# SKY13575-639LF_1to4.net
KiCad netlist of a schematic drawn in EasyEDA Pro
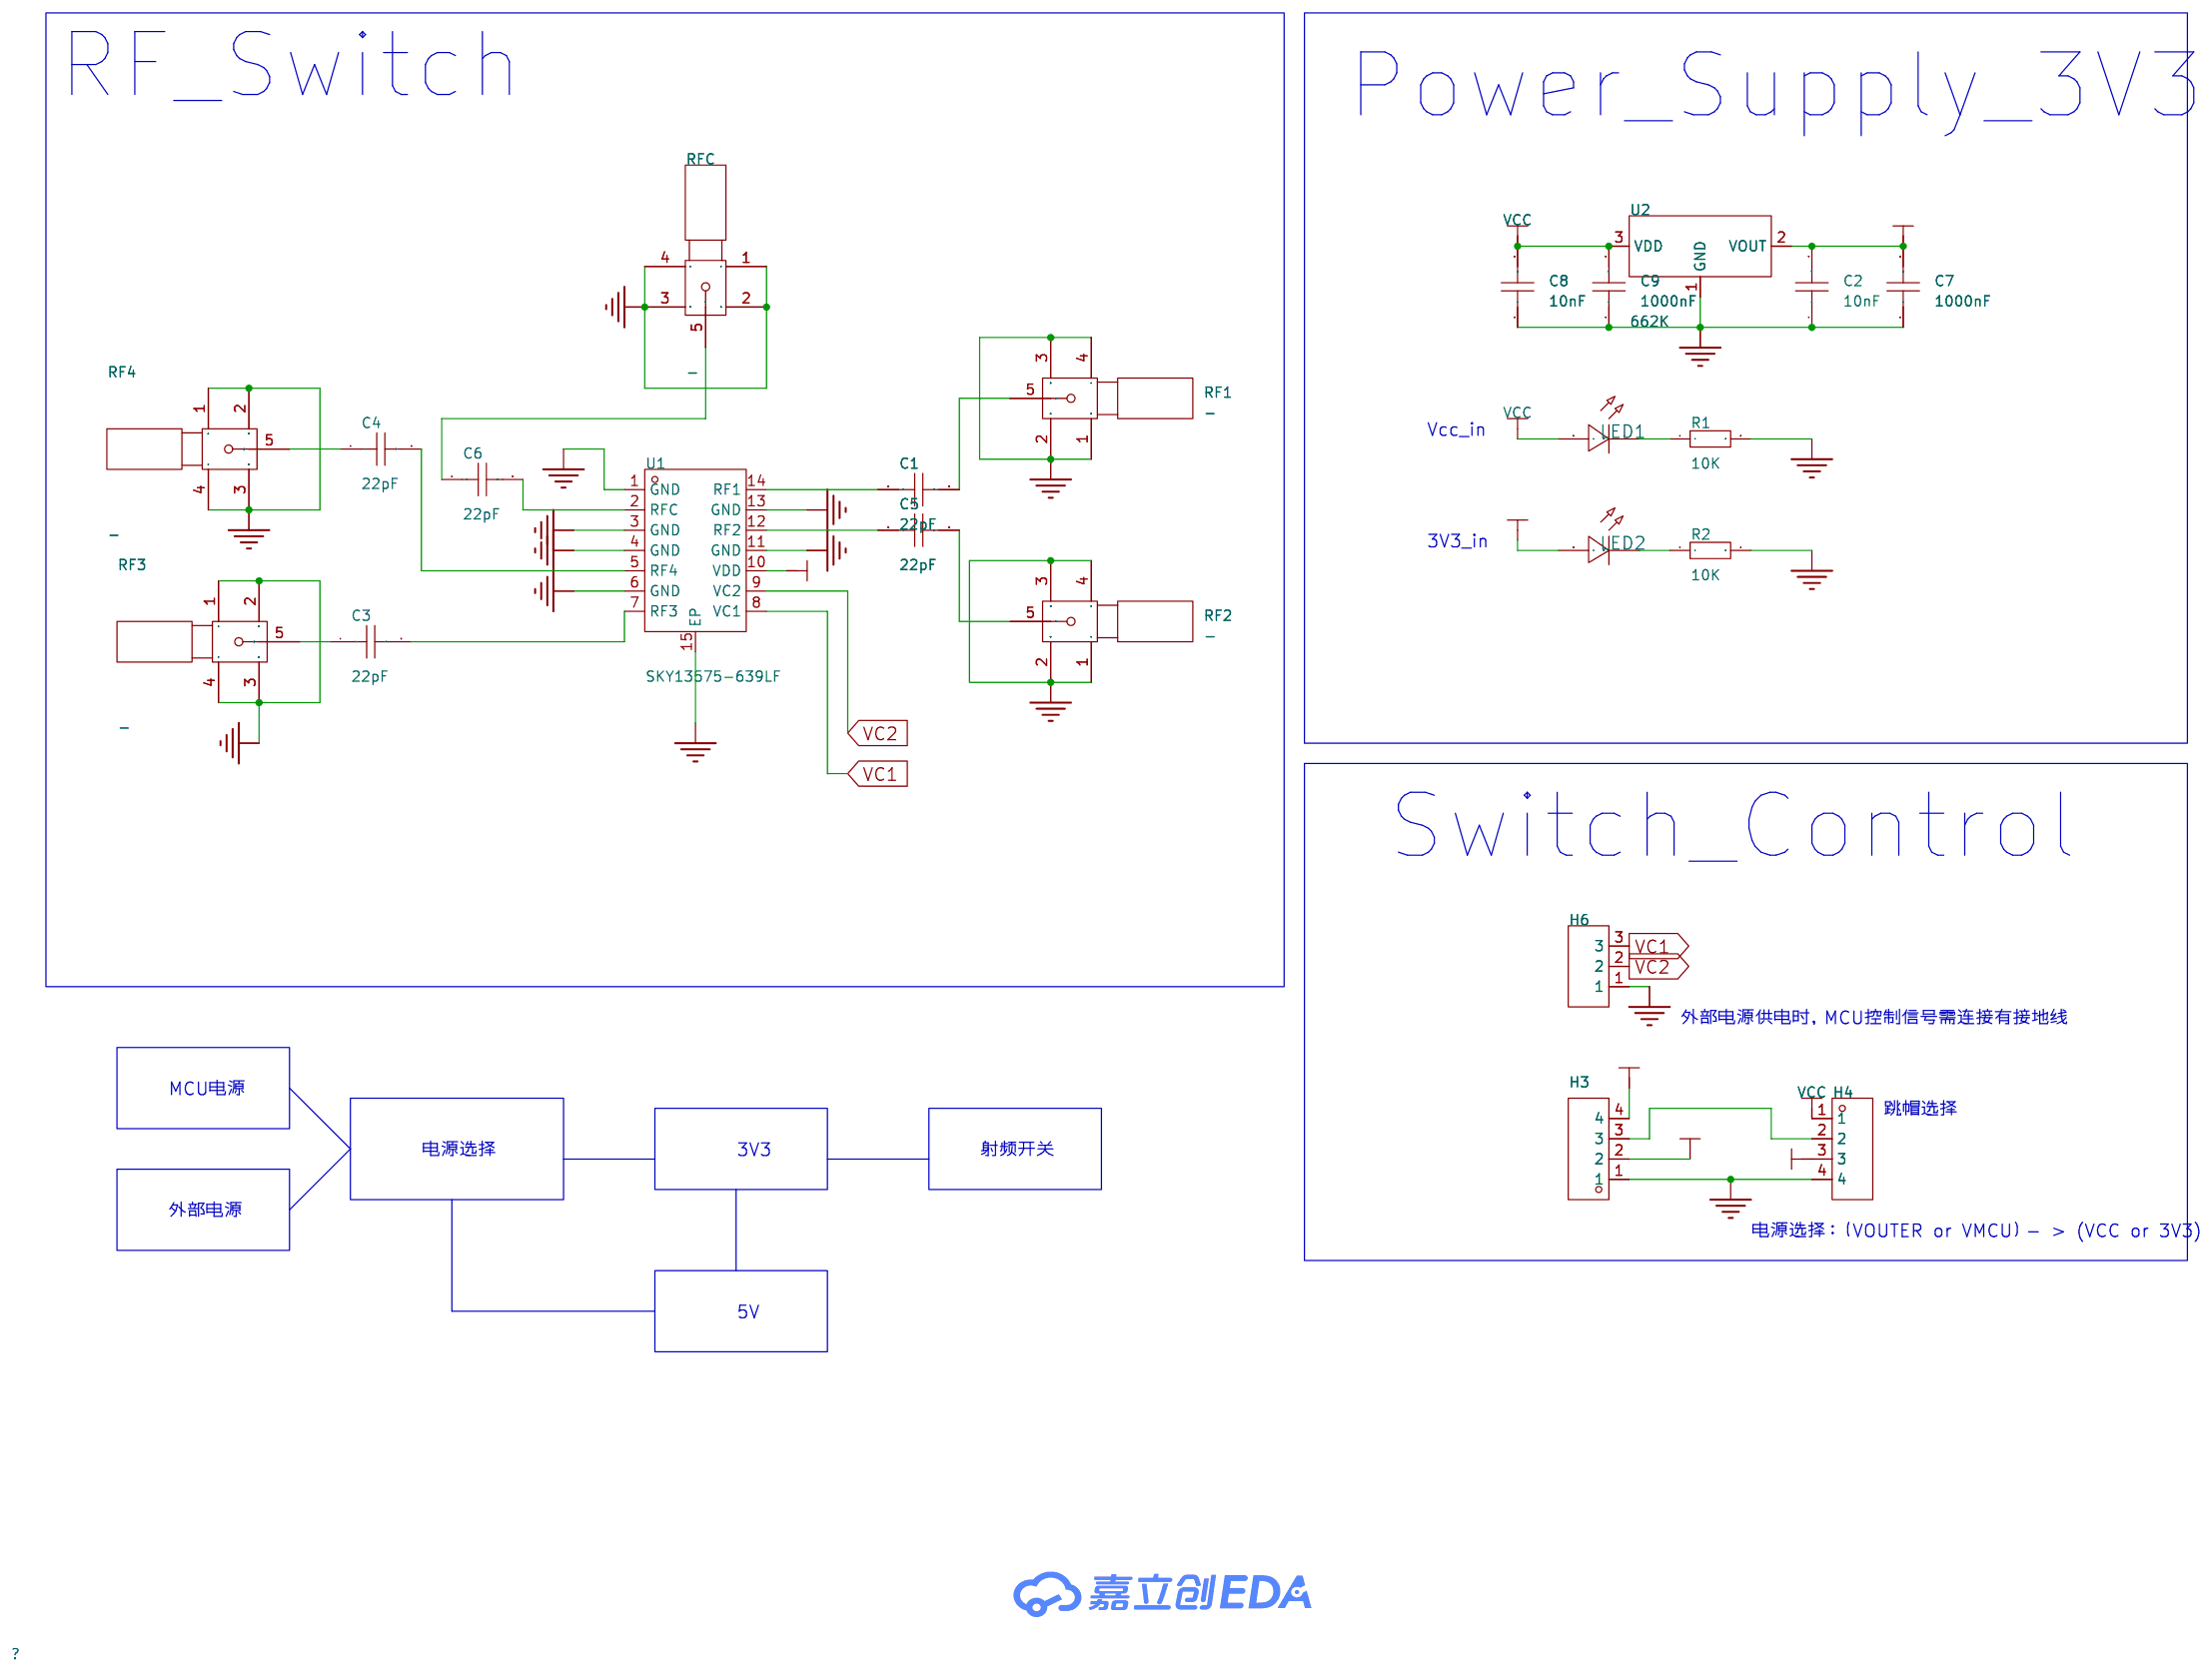
[diagram p0: schematic sheet]

(export (version "E")
  (design (tool "Eeschema 10.0.6"))
  (components
    (comp (ref "C1")
      (value "22pF")
      (footprint "easyedapro:C0603")
      (libsource (lib "easyedapro") (part "Capacitance"))
    )
    (comp (ref "C2")
      (value "10nF")
      (footprint "easyedapro:C0603")
      (libsource (lib "easyedapro") (part "Capacitance"))
    )
    (comp (ref "C3")
      (value "22pF")
      (footprint "easyedapro:C0603")
      (libsource (lib "easyedapro") (part "Capacitance"))
    )
    (comp (ref "C4")
      (value "22pF")
      (footprint "easyedapro:C0603")
      (libsource (lib "easyedapro") (part "Capacitance"))
    )
    (comp (ref "C5")
      (value "22pF")
      (footprint "easyedapro:C0603")
      (libsource (lib "easyedapro") (part "Capacitance"))
    )
    (comp (ref "C6")
      (value "22pF")
      (footprint "easyedapro:C0603")
      (libsource (lib "easyedapro") (part "Capacitance"))
    )
    (comp (ref "C7")
      (value "1000nF")
      (footprint "easyedapro:C0603")
      (libsource (lib "easyedapro") (part "Capacitance"))
    )
    (comp (ref "C8")
      (value "10nF")
      (footprint "easyedapro:C0603")
      (libsource (lib "easyedapro") (part "Capacitance"))
    )
    (comp (ref "C9")
      (value "1000nF")
      (footprint "easyedapro:C0603")
      (libsource (lib "easyedapro") (part "Capacitance"))
    )
    (comp (ref "H3")
      (value "~")
      (footprint "easyedapro:HDR-TH_4P-P2.54-V-F")
      (libsource (lib "easyedapro") (part "2.54-1*4P母"))
    )
    (comp (ref "H4")
      (value "~")
      (footprint "easyedapro:HDR-TH_4P-P2.54-V-F")
      (libsource (lib "easyedapro") (part "2.54-1*4P母"))
    )
    (comp (ref "H6")
      (value "~")
      (footprint "easyedapro:HDR-TH_3P-P2.54-V-F")
      (libsource (lib "easyedapro") (part "PM254V-11-03-H85"))
    )
    (comp (ref "LED1")
      (value "~")
      (footprint "easyedapro:LED_0603")
      (libsource (lib "easyedapro") (part "LED_R"))
    )
    (comp (ref "LED2")
      (value "~")
      (footprint "easyedapro:LED_0603")
      (libsource (lib "easyedapro") (part "LED_R"))
    )
    (comp (ref "R1") (value "10K") (footprint "easyedapro:R0603") (libsource (lib "easyedapro") (part "电阻")))
    (comp (ref "R2") (value "10K") (footprint "easyedapro:R0603") (libsource (lib "easyedapro") (part "电阻")))
    (comp (ref "RF1")
      (value "-")
      (footprint "easyedapro:SMA-SMD_BWSMA-KE-P001")
      (description "连接器类型:板端;接口类型:内孔;端口数量:1;接口直径:5.2mm;接口长度/高度:-;频率:-;射频系列:SMA;阻抗:50Ω;样式:偏脚;工作温度:-;")
      (fields
        (field (name "Manufacturer Part") "BWSMA-KE-P001")
        (field (name "Manufacturer") "BAT WIRELESS(蝙蝠无线)")
      )
      (libsource (lib "easyedapro") (part "BWSMA-KE-P001"))
    )
    (comp (ref "RF2")
      (value "-")
      (footprint "easyedapro:SMA-SMD_BWSMA-KE-P001")
      (description "连接器类型:板端;接口类型:内孔;端口数量:1;接口直径:5.2mm;接口长度/高度:-;频率:-;射频系列:SMA;阻抗:50Ω;样式:偏脚;工作温度:-;")
      (fields
        (field (name "Manufacturer Part") "BWSMA-KE-P001")
        (field (name "Manufacturer") "BAT WIRELESS(蝙蝠无线)")
      )
      (libsource (lib "easyedapro") (part "BWSMA-KE-P001"))
    )
    (comp (ref "RF3")
      (value "-")
      (footprint "easyedapro:SMA-SMD_BWSMA-KE-P001")
      (description "连接器类型:板端;接口类型:内孔;端口数量:1;接口直径:5.2mm;接口长度/高度:-;频率:-;射频系列:SMA;阻抗:50Ω;样式:偏脚;工作温度:-;")
      (fields
        (field (name "Manufacturer Part") "BWSMA-KE-P001")
        (field (name "Manufacturer") "BAT WIRELESS(蝙蝠无线)")
      )
      (libsource (lib "easyedapro") (part "BWSMA-KE-P001"))
    )
    (comp (ref "RF4")
      (value "-")
      (footprint "easyedapro:SMA-SMD_BWSMA-KE-P001")
      (description "连接器类型:板端;接口类型:内孔;端口数量:1;接口直径:5.2mm;接口长度/高度:-;频率:-;射频系列:SMA;阻抗:50Ω;样式:偏脚;工作温度:-;")
      (fields
        (field (name "Manufacturer Part") "BWSMA-KE-P001")
        (field (name "Manufacturer") "BAT WIRELESS(蝙蝠无线)")
      )
      (libsource (lib "easyedapro") (part "BWSMA-KE-P001"))
    )
    (comp (ref "RFC")
      (value "-")
      (footprint "easyedapro:SMA-SMD_BWSMA-KE-P001")
      (description "连接器类型:板端;接口类型:内孔;端口数量:1;接口直径:5.2mm;接口长度/高度:-;频率:-;射频系列:SMA;阻抗:50Ω;样式:偏脚;工作温度:-;")
      (fields
        (field (name "Manufacturer Part") "BWSMA-KE-P001")
        (field (name "Manufacturer") "BAT WIRELESS(蝙蝠无线)")
      )
      (libsource (lib "easyedapro") (part "BWSMA-KE-P001"))
    )
    (comp (ref "U1")
      (value "SKY13575-639LF")
      (footprint "easyedapro:QFN-14_L1.6-W1.6-P0.40-BL-EP0.7")
      (fields (field (name "Manufacturer") "SKYWORKS"))
      (libsource (lib "easyedapro") (part "SKY13575-639LF"))
    )
    (comp (ref "U2")
      (value "662K")
      (footprint "easyedapro:SOT-23-3_L2.9-W1.3-P1.90-LS2.4-BR")
      (description "输出类型:固定;工作电压:8V;输出电压:3.3V;输出电流:300mA;电源纹波抑制比(PSRR):40dB@(1kHz);输出极性:正极;")
      (fields (field (name "Manufacturer") "HXY MOSFET(华轩阳电子)"))
      (libsource (lib "easyedapro") (part "662K"))
    )
  )
  (nets
    (net (code "1") (name "3V3") (class "Default")
      (node (ref "C2") (pin "2") (pinfunction "2_2") (pintype "input"))
      (node (ref "C7") (pin "2") (pinfunction "2_2") (pintype "input"))
      (node (ref "H4") (pin "3") (pinfunction "3_3") (pintype "unspecified"))
      (node (ref "LED2") (pin "2") (pinfunction "A_2") (pintype "input"))
      (node (ref "U1") (pin "10") (pinfunction "VDD_10") (pintype "unspecified"))
      (node (ref "U2") (pin "2") (pinfunction "VOUT_2") (pintype "unspecified"))
    )
    (net (code "2") (name "GND") (class "Default")
      (node (ref "C2") (pin "1") (pinfunction "1_1") (pintype "input"))
      (node (ref "C7") (pin "1") (pinfunction "1_1") (pintype "input"))
      (node (ref "C8") (pin "1") (pinfunction "1_1") (pintype "input"))
      (node (ref "C9") (pin "1") (pinfunction "1_1") (pintype "input"))
      (node (ref "H3") (pin "1") (pinfunction "1_1") (pintype "unspecified"))
      (node (ref "H4") (pin "4") (pinfunction "4_4") (pintype "unspecified"))
      (node (ref "H6") (pin "1") (pinfunction "1_1") (pintype "unspecified"))
      (node (ref "R1") (pin "2") (pinfunction "2_2") (pintype "input"))
      (node (ref "R2") (pin "2") (pinfunction "2_2") (pintype "input"))
      (node (ref "RF1") (pin "1") (pinfunction "1_1") (pintype "unspecified"))
      (node (ref "RF1") (pin "2") (pinfunction "2_2") (pintype "unspecified"))
      (node (ref "RF1") (pin "3") (pinfunction "3_3") (pintype "unspecified"))
      (node (ref "RF1") (pin "4") (pinfunction "4_4") (pintype "unspecified"))
      (node (ref "RF2") (pin "1") (pinfunction "1_1") (pintype "unspecified"))
      (node (ref "RF2") (pin "2") (pinfunction "2_2") (pintype "unspecified"))
      (node (ref "RF2") (pin "3") (pinfunction "3_3") (pintype "unspecified"))
      (node (ref "RF2") (pin "4") (pinfunction "4_4") (pintype "unspecified"))
      (node (ref "RF3") (pin "1") (pinfunction "1_1") (pintype "unspecified"))
      (node (ref "RF3") (pin "2") (pinfunction "2_2") (pintype "unspecified"))
      (node (ref "RF3") (pin "3") (pinfunction "3_3") (pintype "unspecified"))
      (node (ref "RF3") (pin "4") (pinfunction "4_4") (pintype "unspecified"))
      (node (ref "RF4") (pin "1") (pinfunction "1_1") (pintype "unspecified"))
      (node (ref "RF4") (pin "2") (pinfunction "2_2") (pintype "unspecified"))
      (node (ref "RF4") (pin "3") (pinfunction "3_3") (pintype "unspecified"))
      (node (ref "RF4") (pin "4") (pinfunction "4_4") (pintype "unspecified"))
      (node (ref "RFC") (pin "1") (pinfunction "1_1") (pintype "unspecified"))
      (node (ref "RFC") (pin "2") (pinfunction "2_2") (pintype "unspecified"))
      (node (ref "RFC") (pin "3") (pinfunction "3_3") (pintype "unspecified"))
      (node (ref "RFC") (pin "4") (pinfunction "4_4") (pintype "unspecified"))
      (node (ref "U1") (pin "1") (pinfunction "GND_1") (pintype "unspecified"))
      (node (ref "U1") (pin "11") (pinfunction "GND_11") (pintype "unspecified"))
      (node (ref "U1") (pin "13") (pinfunction "GND_13") (pintype "unspecified"))
      (node (ref "U1") (pin "15") (pinfunction "EP_15") (pintype "unspecified"))
      (node (ref "U1") (pin "3") (pinfunction "GND_3") (pintype "unspecified"))
      (node (ref "U1") (pin "4") (pinfunction "GND_4") (pintype "unspecified"))
      (node (ref "U1") (pin "6") (pinfunction "GND_6") (pintype "unspecified"))
      (node (ref "U2") (pin "1") (pinfunction "GND_1") (pintype "unspecified"))
    )
    (net (code "3") (name "Net-(C1-Pad2)") (class "Default")
      (node (ref "C1") (pin "2") (pinfunction "2_2") (pintype "input"))
      (node (ref "RF1") (pin "5") (pinfunction "5_5") (pintype "unspecified"))
    )
    (net (code "4") (name "Net-(C3-Pad1)") (class "Default")
      (node (ref "C3") (pin "1") (pinfunction "1_1") (pintype "input"))
      (node (ref "RF3") (pin "5") (pinfunction "5_5") (pintype "unspecified"))
    )
    (net (code "5") (name "Net-(C4-Pad1)") (class "Default")
      (node (ref "C4") (pin "1") (pinfunction "1_1") (pintype "input"))
      (node (ref "RF4") (pin "5") (pinfunction "5_5") (pintype "unspecified"))
    )
    (net (code "6") (name "Net-(C5-Pad2)") (class "Default")
      (node (ref "C5") (pin "2") (pinfunction "2_2") (pintype "input"))
      (node (ref "RF2") (pin "5") (pinfunction "5_5") (pintype "unspecified"))
    )
    (net (code "7") (name "Net-(C6-Pad1)") (class "Default")
      (node (ref "C6") (pin "1") (pinfunction "1_1") (pintype "input"))
      (node (ref "RFC") (pin "5") (pinfunction "5_5") (pintype "unspecified"))
    )
    (net (code "8") (name "Net-(H3-Pad3)") (class "Default")
      (node (ref "H3") (pin "3") (pinfunction "3_3") (pintype "unspecified"))
      (node (ref "H4") (pin "2") (pinfunction "2_2") (pintype "unspecified"))
    )
    (net (code "9") (name "Net-(LED1-C)") (class "Default")
      (node (ref "LED1") (pin "1") (pinfunction "C_1") (pintype "input"))
      (node (ref "R1") (pin "1") (pinfunction "1_1") (pintype "input"))
    )
    (net (code "10") (name "Net-(LED2-C)") (class "Default")
      (node (ref "LED2") (pin "1") (pinfunction "C_1") (pintype "input"))
      (node (ref "R2") (pin "1") (pinfunction "1_1") (pintype "input"))
    )
    (net (code "11") (name "Net-(U1-RF1)") (class "Default")
      (node (ref "C1") (pin "1") (pinfunction "1_1") (pintype "input"))
      (node (ref "U1") (pin "14") (pinfunction "RF1_14") (pintype "unspecified"))
    )
    (net (code "12") (name "Net-(U1-RF2)") (class "Default")
      (node (ref "C5") (pin "1") (pinfunction "1_1") (pintype "input"))
      (node (ref "U1") (pin "12") (pinfunction "RF2_12") (pintype "unspecified"))
    )
    (net (code "13") (name "Net-(U1-RF3)") (class "Default")
      (node (ref "C3") (pin "2") (pinfunction "2_2") (pintype "input"))
      (node (ref "U1") (pin "7") (pinfunction "RF3_7") (pintype "unspecified"))
    )
    (net (code "14") (name "Net-(U1-RF4)") (class "Default")
      (node (ref "C4") (pin "2") (pinfunction "2_2") (pintype "input"))
      (node (ref "U1") (pin "5") (pinfunction "RF4_5") (pintype "unspecified"))
    )
    (net (code "15") (name "Net-(U1-RFC)") (class "Default")
      (node (ref "C6") (pin "2") (pinfunction "2_2") (pintype "input"))
      (node (ref "U1") (pin "2") (pinfunction "RFC_2") (pintype "unspecified"))
    )
    (net (code "16") (name "VC1") (class "Default")
      (node (ref "H6") (pin "3") (pinfunction "3_3") (pintype "unspecified"))
      (node (ref "U1") (pin "8") (pinfunction "VC1_8") (pintype "unspecified"))
    )
    (net (code "17") (name "VC2") (class "Default")
      (node (ref "H6") (pin "2") (pinfunction "2_2") (pintype "unspecified"))
      (node (ref "U1") (pin "9") (pinfunction "VC2_9") (pintype "unspecified"))
    )
    (net (code "18") (name "VCC") (class "Default")
      (node (ref "C8") (pin "2") (pinfunction "2_2") (pintype "input"))
      (node (ref "C9") (pin "2") (pinfunction "2_2") (pintype "input"))
      (node (ref "H4") (pin "1") (pinfunction "1_1") (pintype "unspecified"))
      (node (ref "LED1") (pin "2") (pinfunction "A_2") (pintype "input"))
      (node (ref "U2") (pin "3") (pinfunction "VDD_3") (pintype "unspecified"))
    )
    (net (code "19") (name "VMCU") (class "Default")
      (node (ref "H3") (pin "2") (pinfunction "2_2") (pintype "unspecified"))
    )
    (net (code "20") (name "VOUTER") (class "Default")
      (node (ref "H3") (pin "4") (pinfunction "4_4") (pintype "unspecified"))
    )
  )
)
